# PALM_CONNECTOR.net
KiCad netlist of a schematic drawn in Altium Designer
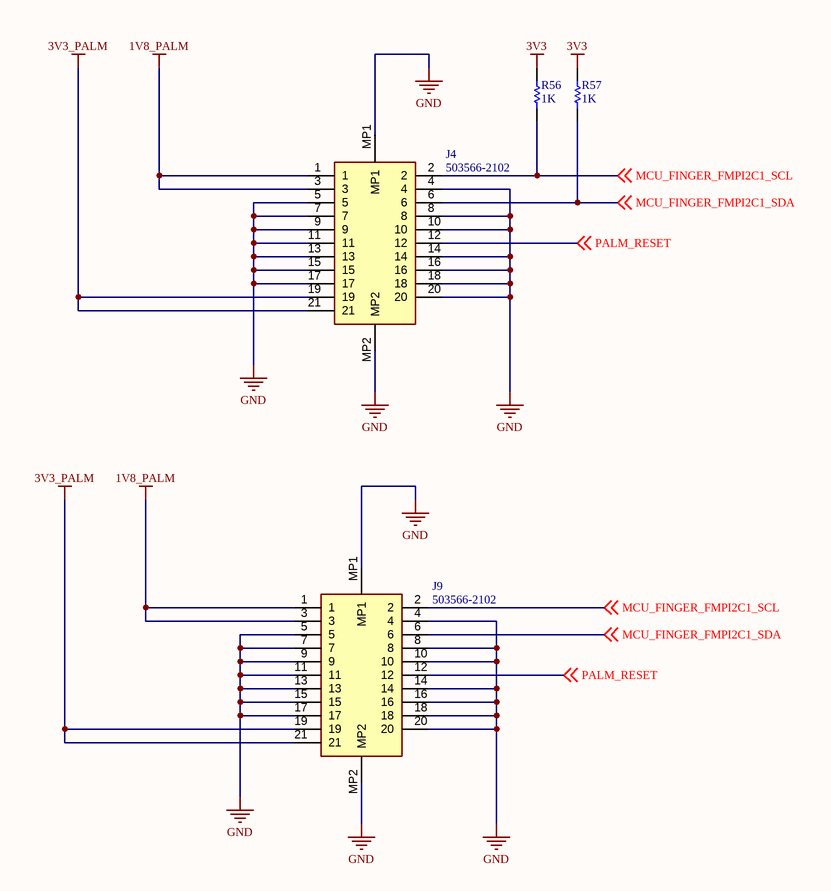
[diagram p0: PALM_CONNECTOR.SchDoc]

(export (version "E")
  (design (tool "Eeschema 10.0.6"))
  (components
    (comp (ref "J4")
      (value "503566-2102")
      (footprint "SamacSys:5035662102")
      (description "Connector")
      (fields (field (name "MOUSER PART NUMBER") "538-503566-2102"))
      (libsource (lib "*") (part "503566-2102"))
    )
    (comp (ref "J9")
      (value "503566-2102")
      (footprint "SamacSys:5035662102")
      (description "Connector")
      (fields (field (name "MOUSER PART NUMBER") "538-503566-2102"))
      (libsource (lib "*") (part "503566-2102"))
    )
    (comp (ref "R56")
      (value "1K")
      (footprint "RESC1005X40X25LL05T10")
      (fields (field (name "PART NUMBER") "RC0402JR-071KL") (field (name "MANUFACTURER") "Yageo / Phycomp"))
      (libsource (lib "Altium Content Vault") (part "RES"))
    )
    (comp (ref "R57")
      (value "1K")
      (footprint "RESC1005X40X25LL05T10")
      (fields (field (name "PART NUMBER") "RC0402JR-071KL") (field (name "MANUFACTURER") "Yageo / Phycomp"))
      (libsource (lib "Altium Content Vault") (part "RES"))
    )
  )
  (nets
    (net (code "1") (name "1V8_PALM") (class "Default")
      (node (ref "J4") (pin "1") (pinfunction "1_1") (pintype "passive"))
      (node (ref "J4") (pin "3") (pinfunction "3_3") (pintype "passive"))
      (node (ref "J9") (pin "1") (pinfunction "1_1") (pintype "passive"))
      (node (ref "J9") (pin "3") (pinfunction "3_3") (pintype "passive"))
    )
    (net (code "2") (name "3V3") (class "Default")
      (node (ref "R56") (pin "2") (pinfunction "2_2") (pintype "passive"))
      (node (ref "R57") (pin "2") (pinfunction "2_2") (pintype "passive"))
    )
    (net (code "3") (name "3V3_PALM") (class "Default")
      (node (ref "J4") (pin "19") (pinfunction "19_19") (pintype "passive"))
      (node (ref "J4") (pin "21") (pinfunction "21_21") (pintype "passive"))
      (node (ref "J9") (pin "19") (pinfunction "19_19") (pintype "passive"))
      (node (ref "J9") (pin "21") (pinfunction "21_21") (pintype "passive"))
    )
    (net (code "4") (name "GND") (class "Default")
      (node (ref "J4") (pin "10") (pinfunction "10_10") (pintype "passive"))
      (node (ref "J4") (pin "11") (pinfunction "11_11") (pintype "passive"))
      (node (ref "J4") (pin "13") (pinfunction "13_13") (pintype "passive"))
      (node (ref "J4") (pin "14") (pinfunction "14_14") (pintype "passive"))
      (node (ref "J4") (pin "15") (pinfunction "15_15") (pintype "passive"))
      (node (ref "J4") (pin "16") (pinfunction "16_16") (pintype "passive"))
      (node (ref "J4") (pin "17") (pinfunction "17_17") (pintype "passive"))
      (node (ref "J4") (pin "18") (pinfunction "18_18") (pintype "passive"))
      (node (ref "J4") (pin "20") (pinfunction "20_20") (pintype "passive"))
      (node (ref "J4") (pin "4") (pinfunction "4_4") (pintype "passive"))
      (node (ref "J4") (pin "5") (pinfunction "5_5") (pintype "passive"))
      (node (ref "J4") (pin "7") (pinfunction "7_7") (pintype "passive"))
      (node (ref "J4") (pin "8") (pinfunction "8_8") (pintype "passive"))
      (node (ref "J4") (pin "9") (pinfunction "9_9") (pintype "passive"))
      (node (ref "J4") (pin "MP1") (pinfunction "MP1_MP1") (pintype "passive"))
      (node (ref "J4") (pin "MP2") (pinfunction "MP2_MP2") (pintype "passive"))
      (node (ref "J9") (pin "10") (pinfunction "10_10") (pintype "passive"))
      (node (ref "J9") (pin "11") (pinfunction "11_11") (pintype "passive"))
      (node (ref "J9") (pin "13") (pinfunction "13_13") (pintype "passive"))
      (node (ref "J9") (pin "14") (pinfunction "14_14") (pintype "passive"))
      (node (ref "J9") (pin "15") (pinfunction "15_15") (pintype "passive"))
      (node (ref "J9") (pin "16") (pinfunction "16_16") (pintype "passive"))
      (node (ref "J9") (pin "17") (pinfunction "17_17") (pintype "passive"))
      (node (ref "J9") (pin "18") (pinfunction "18_18") (pintype "passive"))
      (node (ref "J9") (pin "20") (pinfunction "20_20") (pintype "passive"))
      (node (ref "J9") (pin "4") (pinfunction "4_4") (pintype "passive"))
      (node (ref "J9") (pin "5") (pinfunction "5_5") (pintype "passive"))
      (node (ref "J9") (pin "7") (pinfunction "7_7") (pintype "passive"))
      (node (ref "J9") (pin "8") (pinfunction "8_8") (pintype "passive"))
      (node (ref "J9") (pin "9") (pinfunction "9_9") (pintype "passive"))
      (node (ref "J9") (pin "MP1") (pinfunction "MP1_MP1") (pintype "passive"))
      (node (ref "J9") (pin "MP2") (pinfunction "MP2_MP2") (pintype "passive"))
    )
    (net (code "5") (name "MCU_FINGER_FMPI2C1_SCL") (class "Default")
      (node (ref "J4") (pin "2") (pinfunction "2_2") (pintype "passive"))
      (node (ref "J9") (pin "2") (pinfunction "2_2") (pintype "passive"))
      (node (ref "R56") (pin "1") (pinfunction "1_1") (pintype "passive"))
    )
    (net (code "6") (name "MCU_FINGER_FMPI2C1_SDA") (class "Default")
      (node (ref "J4") (pin "6") (pinfunction "6_6") (pintype "passive"))
      (node (ref "J9") (pin "6") (pinfunction "6_6") (pintype "passive"))
      (node (ref "R57") (pin "1") (pinfunction "1_1") (pintype "passive"))
    )
    (net (code "7") (name "PALM_RESET") (class "Default")
      (node (ref "J4") (pin "12") (pinfunction "12_12") (pintype "passive"))
      (node (ref "J9") (pin "12") (pinfunction "12_12") (pintype "passive"))
    )
  )
)
